# DrudePower.net
KiCad netlist of a schematic drawn in Altium Designer
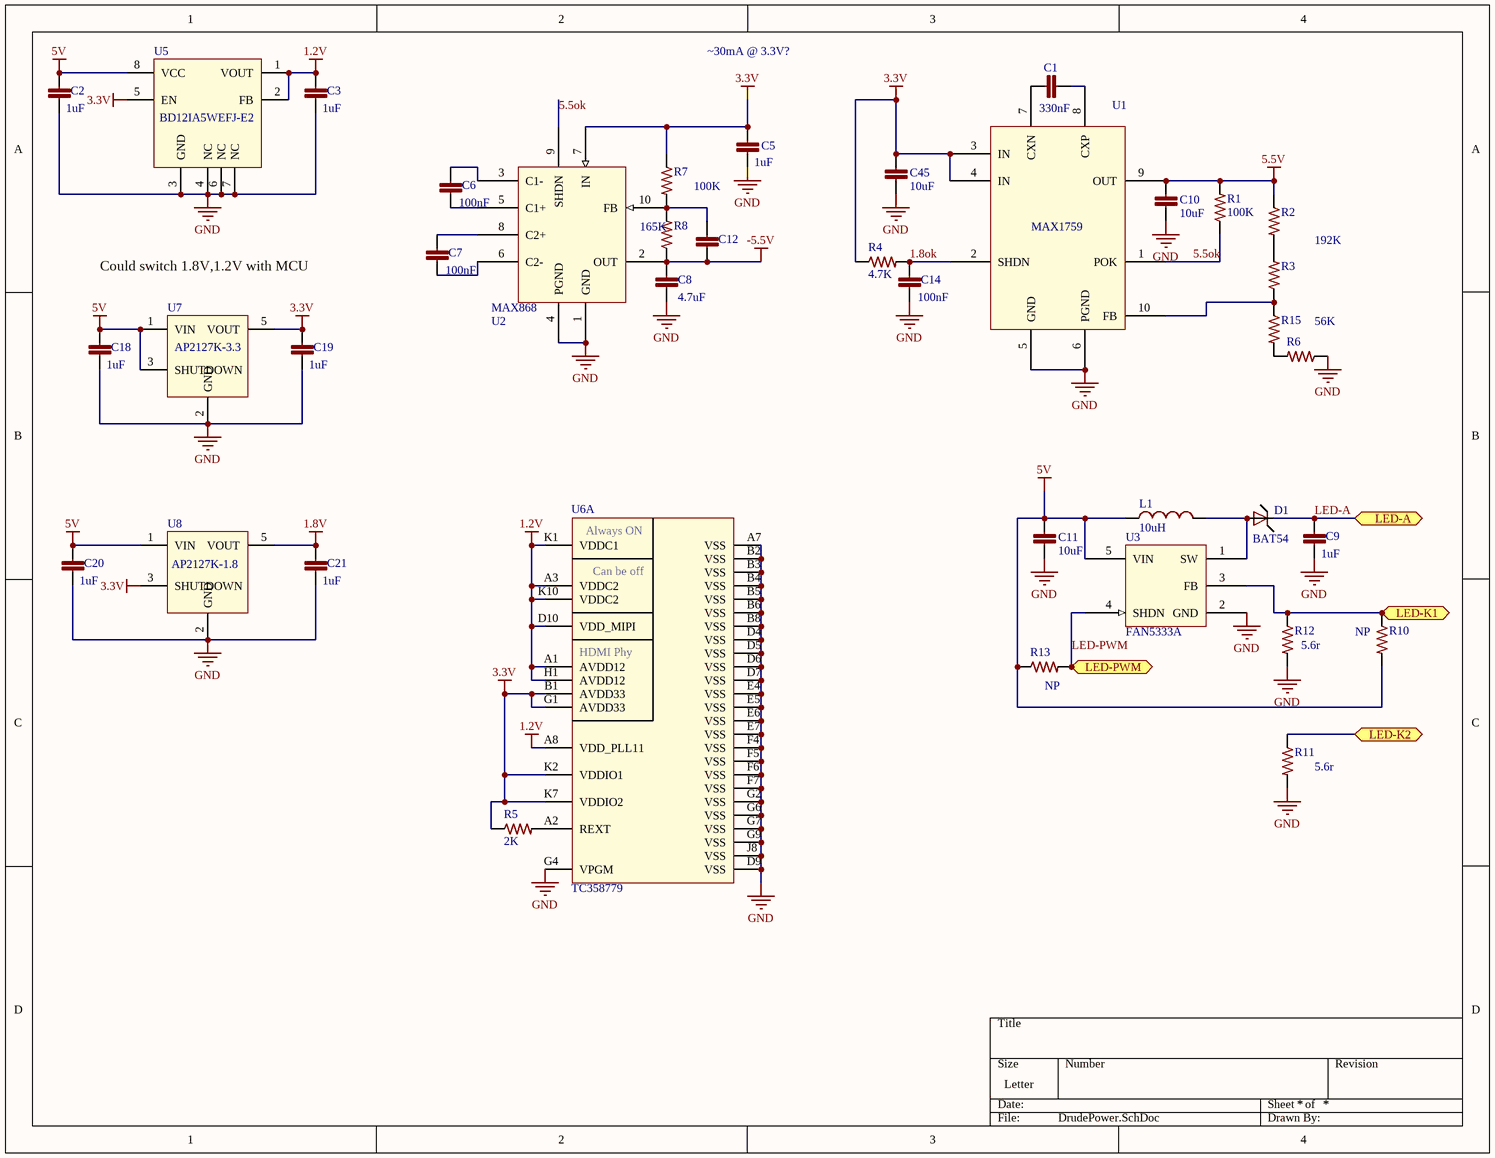
[diagram p0: DrudePower.SchDoc]

(export (version "E")
  (design (tool "Eeschema 10.0.6"))
  (components
    (comp (ref "C1")
      (value "330nF")
      (footprint "C0603")
      (description "CAP CER 0603 330nF 50V 10% X7R")
      (fields
        (field (name "MANUFACTURERPARTNUMBER") "C1608X7R1H334K080AC")
        (field (name "PUBLISHER") "UltiMachine")
      )
      (libsource (lib "hmi") (part "C1608X7R1H334K080AC"))
    )
    (comp (ref "C2")
      (value "1uF")
      (footprint "C0603")
      (description "CAP CER 0603 1uF 10V Y5V")
      (fields
        (field (name "MANUFACTURERPARTNUMBER") "CC0603ZRY5V6BB105")
        (field (name "PUBLISHER") "UltiMachine")
      )
      (libsource (lib "3Delight") (part "CC0603ZRY5V6BB105"))
    )
    (comp (ref "C3")
      (value "1uF")
      (footprint "C0603")
      (description "CAP CER 0603 1uF 10V Y5V")
      (fields
        (field (name "MANUFACTURERPARTNUMBER") "CC0603ZRY5V6BB105")
        (field (name "PUBLISHER") "UltiMachine")
      )
      (libsource (lib "3Delight") (part "CC0603ZRY5V6BB105"))
    )
    (comp (ref "C5")
      (value "1uF")
      (footprint "C0603")
      (description "CAP CER 0603 1uF 10V Y5V")
      (fields
        (field (name "MANUFACTURERPARTNUMBER") "CC0603ZRY5V6BB105")
        (field (name "PUBLISHER") "UltiMachine")
      )
      (libsource (lib "3Delight") (part "CC0603ZRY5V6BB105"))
    )
    (comp (ref "C6")
      (value "100nF")
      (footprint "C0603")
      (description "CAP CER 0603 100nF 50V 10% X7R")
      (fields
        (field (name "MANUFACTURERPARTNUMBER") "C0603C104K5RACTU")
        (field (name "PUBLISHER") "UltiMachine")
      )
      (libsource (lib "3Delight") (part "C0603C104K5RACTU"))
    )
    (comp (ref "C7")
      (value "100nF")
      (footprint "C0603")
      (description "CAP CER 0603 100nF 50V 10% X7R")
      (fields
        (field (name "MANUFACTURERPARTNUMBER") "C0603C104K5RACTU")
        (field (name "PUBLISHER") "UltiMachine")
      )
      (libsource (lib "3Delight") (part "C0603C104K5RACTU"))
    )
    (comp (ref "C8")
      (value "4.7uF")
      (footprint "C1206")
      (description "CAP CER 1206 4.7uF 50V 10% X7R")
      (fields
        (field (name "MANUFACTURERPARTNUMBER") "GRM31CR71H475KA12L")
        (field (name "PUBLISHER") "UltiMachine")
      )
      (libsource (lib "3Delight") (part "GRM31CR71H475KA12L"))
    )
    (comp (ref "C9")
      (value "1uF")
      (footprint "C0805")
      (description "CAP CER 0805 1uF 50V 10% X7R")
      (fields
        (field (name "MANUFACTURERPARTNUMBER") "GRM21BR71H105KA12L")
        (field (name "PUBLISHER") "UltiMachine")
      )
      (libsource (lib "3Delight") (part "GRM21BR71H105KA12L"))
    )
    (comp (ref "C10")
      (value "10uF")
      (footprint "C0805")
      (description "CAP CER 0805 10uF 10V 10% X5R")
      (fields
        (field (name "MANUFACTURERPARTNUMBER") "C0805C106K8PACTU")
        (field (name "PUBLISHER") "UltiMachine")
      )
      (libsource (lib "3Delight") (part "C0805C106K8PACTU"))
    )
    (comp (ref "C11")
      (value "10uF")
      (footprint "C0805")
      (description "CAP CER 0805 10uF 10V 10% X5R")
      (fields
        (field (name "MANUFACTURERPARTNUMBER") "C0805C106K8PACTU")
        (field (name "PUBLISHER") "UltiMachine")
      )
      (libsource (lib "3Delight") (part "C0805C106K8PACTU"))
    )
    (comp (ref "C12")
      (value "~")
      (footprint "C0603")
      (description "Capacitor Non Polarized")
      (fields (field (name "PUBLISHER") "UltiMachine"))
      (libsource (lib "3Delight") (part "Capacitor"))
    )
    (comp (ref "C14")
      (value "100nF")
      (footprint "C0603")
      (description "CAP CER 0603 100nF 50V 10% X7R")
      (fields
        (field (name "MANUFACTURERPARTNUMBER") "C0603C104K5RACTU")
        (field (name "PUBLISHER") "UltiMachine")
      )
      (libsource (lib "3Delight") (part "C0603C104K5RACTU"))
    )
    (comp (ref "C18")
      (value "1uF")
      (footprint "C0603")
      (description "CAP CER 0603 1uF 10V Y5V")
      (fields
        (field (name "MANUFACTURERPARTNUMBER") "CC0603ZRY5V6BB105")
        (field (name "PUBLISHER") "UltiMachine")
      )
      (libsource (lib "3Delight") (part "CC0603ZRY5V6BB105"))
    )
    (comp (ref "C19")
      (value "1uF")
      (footprint "C0603")
      (description "CAP CER 0603 1uF 10V Y5V")
      (fields
        (field (name "MANUFACTURERPARTNUMBER") "CC0603ZRY5V6BB105")
        (field (name "PUBLISHER") "UltiMachine")
      )
      (libsource (lib "3Delight") (part "CC0603ZRY5V6BB105"))
    )
    (comp (ref "C20")
      (value "1uF")
      (footprint "C0603")
      (description "CAP CER 0603 1uF 10V Y5V")
      (fields
        (field (name "MANUFACTURERPARTNUMBER") "CC0603ZRY5V6BB105")
        (field (name "PUBLISHER") "UltiMachine")
      )
      (libsource (lib "3Delight") (part "CC0603ZRY5V6BB105"))
    )
    (comp (ref "C21")
      (value "1uF")
      (footprint "C0603")
      (description "CAP CER 0603 1uF 10V Y5V")
      (fields
        (field (name "MANUFACTURERPARTNUMBER") "CC0603ZRY5V6BB105")
        (field (name "PUBLISHER") "UltiMachine")
      )
      (libsource (lib "3Delight") (part "CC0603ZRY5V6BB105"))
    )
    (comp (ref "C45")
      (value "10uF")
      (footprint "C0805")
      (description "CAP CER 0805 10uF 10V 10% X5R")
      (fields
        (field (name "MANUFACTURERPARTNUMBER") "C0805C106K8PACTU")
        (field (name "PUBLISHER") "UltiMachine")
      )
      (libsource (lib "3Delight") (part "C0805C106K8PACTU"))
    )
    (comp (ref "D1")
      (value "BAT54")
      (footprint "SOD523")
      (description "Diode Schottky 30V 200mA")
      (libsource (lib "hmi") (part "BAT54XV2"))
    )
    (comp (ref "L1")
      (value "10uH")
      (footprint "INDP3027X15L")
      (description "Ind 10uH 1A")
      (libsource (lib "hmi") (part "SRN3015-100M"))
    )
    (comp (ref "R1")
      (value "100K")
      (footprint "R0603")
      (description "RES 100K OHM 1/10W 1% 0603 SMD")
      (fields
        (field (name "MANUFACTURERPARTNUMBER") "RC0603FR-07100KL")
        (field (name "PUBLISHER") "UltiMachine")
      )
      (libsource (lib "3Delight") (part "RC0603FR-07100KL"))
    )
    (comp (ref "R2")
      (value "~")
      (footprint "R0603")
      (description "Resistor")
      (fields (field (name "PUBLISHER") "UltiMachine"))
      (libsource (lib "3Delight") (part "Resistor"))
    )
    (comp (ref "R3")
      (value "~")
      (footprint "R0603")
      (description "Resistor")
      (fields (field (name "PUBLISHER") "UltiMachine"))
      (libsource (lib "3Delight") (part "Resistor"))
    )
    (comp (ref "R4")
      (value "4.7K")
      (footprint "R0603")
      (description "RES 0603 4.7K 100mW 1%")
      (fields (field (name "MANUFACTURERPARTNUMBER") "ERJ3EKF4701V") (field (name "PUBLISHER") "UltiMachine"))
      (libsource (lib "3Delight") (part "ERJ3EKF4701V"))
    )
    (comp (ref "R5")
      (value "2K")
      (footprint "R0402")
      (description "RES SMD 2K OHM 1% 1/16W 0402")
      (fields
        (field (name "MANUFACTURERPARTNUMBER") "RC0402FR-0710KP")
        (field (name "PUBLISHER") "UltiMachine")
      )
      (libsource (lib "3Delight") (part "RC0402FR-072KL"))
    )
    (comp (ref "R6")
      (value "~")
      (footprint "R0603")
      (description "Resistor")
      (fields (field (name "PUBLISHER") "UltiMachine"))
      (libsource (lib "3Delight") (part "Resistor"))
    )
    (comp (ref "R7")
      (value "~")
      (footprint "R0603")
      (description "Resistor")
      (fields (field (name "PUBLISHER") "UltiMachine"))
      (libsource (lib "3Delight") (part "Resistor"))
    )
    (comp (ref "R8")
      (value "~")
      (footprint "R0603")
      (description "Resistor")
      (fields (field (name "PUBLISHER") "UltiMachine"))
      (libsource (lib "3Delight") (part "Resistor"))
    )
    (comp (ref "R10")
      (value "~")
      (footprint "R0603")
      (description "Resistor")
      (fields (field (name "PUBLISHER") "UltiMachine"))
      (libsource (lib "3Delight") (part "Resistor"))
    )
    (comp (ref "R11")
      (value "~")
      (footprint "R0603")
      (description "Resistor")
      (fields (field (name "PUBLISHER") "UltiMachine"))
      (libsource (lib "3Delight") (part "Resistor"))
    )
    (comp (ref "R12")
      (value "~")
      (footprint "R0603")
      (description "Resistor")
      (fields (field (name "PUBLISHER") "UltiMachine"))
      (libsource (lib "3Delight") (part "Resistor"))
    )
    (comp (ref "R13")
      (value "~")
      (footprint "R0603")
      (description "Resistor")
      (fields (field (name "PUBLISHER") "UltiMachine"))
      (libsource (lib "3Delight") (part "Resistor"))
    )
    (comp (ref "R15")
      (value "~")
      (footprint "R0603")
      (description "Resistor")
      (fields (field (name "PUBLISHER") "UltiMachine"))
      (libsource (lib "3Delight") (part "Resistor"))
    )
    (comp (ref "U1")
      (value "MAX1759")
      (footprint "TSSOP50P490X109-10L")
      (description "Buck/Boost Regulating Charge Pump")
      (libsource (lib "hmi") (part "MAX1759"))
    )
    (comp (ref "U2")
      (value "MAX868")
      (footprint "TSSOP50P490X109-10L")
      (description "Regulated -2x Inverting Charge Pump")
      (libsource (lib "hmi") (part "MAX868"))
    )
    (comp (ref "U3")
      (value "FAN5333A")
      (footprint "SOT95P270X145-5L")
      (description "LED Driver w/ integrated switch")
      (libsource (lib "hmi") (part "FAN5333"))
    )
    (comp (ref "U5")
      (value "BD12IA5WEFJ-E2")
      (footprint "TSOP-HTSOP-J8-127P600X100_HS-9M")
      (description "LDO Regulator 500mA 1.2V")
      (libsource (lib "hmi") (part "BD12IA5WEFJ-E2"))
    )
    (comp (ref "U6")
      (value "TC358779")
      (footprint "BGA80-0707-065")
      (libsource (lib "hmi") (part "TC358779"))
    )
    (comp (ref "U7")
      (value "AP2127K-3.3")
      (footprint "hmi:SOT23-5P285X140-5L")
      (description "LDO 3.3V 0.3A SOT25")
      (libsource (lib "hmi") (part "AP2127K-3.3TRG1"))
    )
    (comp (ref "U8")
      (value "AP2127K-1.8")
      (footprint "hmi:SOT23-5P285X140-5L")
      (description "LDO 1.8V 0.3A SOT25")
      (libsource (lib "hmi") (part "AP2127K-1.8TRG1"))
    )
  )
  (nets
    (net (code "1") (name "-5.5V") (class "Default")
      (node (ref "C12") (pin "2") (pinfunction "2_2") (pintype "passive"))
      (node (ref "C8") (pin "1") (pinfunction "1_1") (pintype "passive"))
      (node (ref "R8") (pin "1") (pinfunction "1_1") (pintype "passive"))
      (node (ref "U2") (pin "2") (pinfunction "OUT_2") (pintype "passive"))
    )
    (net (code "2") (name "/1.8ok") (class "Default")
      (node (ref "C14") (pin "1") (pinfunction "1_1") (pintype "passive"))
      (node (ref "R4") (pin "2") (pinfunction "2_2") (pintype "passive"))
      (node (ref "U1") (pin "2") (pinfunction "SHDN_2") (pintype "passive"))
    )
    (net (code "3") (name "/5.5ok") (class "Default")
      (node (ref "R1") (pin "1") (pinfunction "1_1") (pintype "passive"))
      (node (ref "U1") (pin "1") (pinfunction "POK_1") (pintype "passive"))
      (node (ref "U2") (pin "9") (pinfunction "SHDN_9") (pintype "passive"))
    )
    (net (code "4") (name "/LED-A") (class "Default")
      (node (ref "C9") (pin "1") (pinfunction "1_1") (pintype "passive"))
      (node (ref "D1") (pin "C") (pinfunction "C_C") (pintype "passive"))
    )
    (net (code "5") (name "/LED-K1") (class "Default")
      (node (ref "R10") (pin "1") (pinfunction "1_1") (pintype "passive"))
      (node (ref "R12") (pin "1") (pinfunction "1_1") (pintype "passive"))
      (node (ref "U3") (pin "3") (pinfunction "FB_3") (pintype "passive"))
    )
    (net (code "6") (name "/LED-K2") (class "Default")
      (node (ref "R11") (pin "1") (pinfunction "1_1") (pintype "passive"))
    )
    (net (code "7") (name "/LED-PWM") (class "Default")
      (node (ref "R13") (pin "2") (pinfunction "2_2") (pintype "passive"))
      (node (ref "U3") (pin "4") (pinfunction "SHDN_4") (pintype "input"))
    )
    (net (code "8") (name "1.2V") (class "Default")
      (node (ref "C3") (pin "1") (pinfunction "1_1") (pintype "passive"))
      (node (ref "U5") (pin "1") (pinfunction "VOUT_1") (pintype "power_in"))
      (node (ref "U5") (pin "2") (pinfunction "FB_2") (pintype "power_in"))
      (node (ref "U6") (pin "A1") (pinfunction "AVDD12_A1") (pintype "power_in"))
      (node (ref "U6") (pin "A3") (pinfunction "VDDC2_A3") (pintype "power_in"))
      (node (ref "U6") (pin "A8") (pinfunction "VDD_PLL11_A8") (pintype "power_in"))
      (node (ref "U6") (pin "D10") (pinfunction "VDD_MIPI_D10") (pintype "power_in"))
      (node (ref "U6") (pin "H1") (pinfunction "AVDD12_H1") (pintype "power_in"))
      (node (ref "U6") (pin "K1") (pinfunction "VDDC1_K1") (pintype "power_in"))
      (node (ref "U6") (pin "K10") (pinfunction "VDDC2_K10") (pintype "power_in"))
    )
    (net (code "9") (name "1.8V") (class "Default")
      (node (ref "C21") (pin "1") (pinfunction "1_1") (pintype "passive"))
      (node (ref "U8") (pin "5") (pinfunction "VOUT_5") (pintype "power_in"))
    )
    (net (code "10") (name "3.3V") (class "Default")
      (node (ref "C19") (pin "1") (pinfunction "1_1") (pintype "passive"))
      (node (ref "C45") (pin "1") (pinfunction "1_1") (pintype "passive"))
      (node (ref "C5") (pin "1") (pinfunction "1_1") (pintype "passive"))
      (node (ref "R4") (pin "1") (pinfunction "1_1") (pintype "passive"))
      (node (ref "R5") (pin "1") (pinfunction "1_1") (pintype "passive"))
      (node (ref "R7") (pin "1") (pinfunction "1_1") (pintype "passive"))
      (node (ref "U1") (pin "3") (pinfunction "IN_3") (pintype "power_in"))
      (node (ref "U1") (pin "4") (pinfunction "IN_4") (pintype "power_in"))
      (node (ref "U2") (pin "7") (pinfunction "IN_7") (pintype "input"))
      (node (ref "U5") (pin "5") (pinfunction "EN_5") (pintype "power_in"))
      (node (ref "U6") (pin "B1") (pinfunction "AVDD33_B1") (pintype "power_in"))
      (node (ref "U6") (pin "G1") (pinfunction "AVDD33_G1") (pintype "power_in"))
      (node (ref "U6") (pin "K2") (pinfunction "VDDIO1_K2") (pintype "power_in"))
      (node (ref "U6") (pin "K7") (pinfunction "VDDIO2_K7") (pintype "power_in"))
      (node (ref "U7") (pin "5") (pinfunction "VOUT_5") (pintype "power_in"))
      (node (ref "U8") (pin "3") (pinfunction "SHUTDOWN_3") (pintype "power_in"))
    )
    (net (code "11") (name "5.5V") (class "Default")
      (node (ref "C10") (pin "1") (pinfunction "1_1") (pintype "passive"))
      (node (ref "R1") (pin "2") (pinfunction "2_2") (pintype "passive"))
      (node (ref "R2") (pin "1") (pinfunction "1_1") (pintype "passive"))
      (node (ref "U1") (pin "9") (pinfunction "OUT_9") (pintype "power_in"))
    )
    (net (code "12") (name "5V") (class "Default")
      (node (ref "C11") (pin "1") (pinfunction "1_1") (pintype "passive"))
      (node (ref "C18") (pin "1") (pinfunction "1_1") (pintype "passive"))
      (node (ref "C2") (pin "1") (pinfunction "1_1") (pintype "passive"))
      (node (ref "C20") (pin "1") (pinfunction "1_1") (pintype "passive"))
      (node (ref "L1") (pin "1") (pinfunction "1_1") (pintype "passive"))
      (node (ref "R10") (pin "2") (pinfunction "2_2") (pintype "passive"))
      (node (ref "R13") (pin "1") (pinfunction "1_1") (pintype "passive"))
      (node (ref "U3") (pin "5") (pinfunction "VIN_5") (pintype "power_in"))
      (node (ref "U5") (pin "8") (pinfunction "VCC_8") (pintype "power_in"))
      (node (ref "U7") (pin "1") (pinfunction "VIN_1") (pintype "power_in"))
      (node (ref "U7") (pin "3") (pinfunction "SHUTDOWN_3") (pintype "power_in"))
      (node (ref "U8") (pin "1") (pinfunction "VIN_1") (pintype "power_in"))
    )
    (net (code "13") (name "GND") (class "Default")
      (node (ref "C10") (pin "2") (pinfunction "2_2") (pintype "passive"))
      (node (ref "C11") (pin "2") (pinfunction "2_2") (pintype "passive"))
      (node (ref "C14") (pin "2") (pinfunction "2_2") (pintype "passive"))
      (node (ref "C18") (pin "2") (pinfunction "2_2") (pintype "passive"))
      (node (ref "C19") (pin "2") (pinfunction "2_2") (pintype "passive"))
      (node (ref "C2") (pin "2") (pinfunction "2_2") (pintype "passive"))
      (node (ref "C20") (pin "2") (pinfunction "2_2") (pintype "passive"))
      (node (ref "C21") (pin "2") (pinfunction "2_2") (pintype "passive"))
      (node (ref "C3") (pin "2") (pinfunction "2_2") (pintype "passive"))
      (node (ref "C45") (pin "2") (pinfunction "2_2") (pintype "passive"))
      (node (ref "C5") (pin "2") (pinfunction "2_2") (pintype "passive"))
      (node (ref "C8") (pin "2") (pinfunction "2_2") (pintype "passive"))
      (node (ref "C9") (pin "2") (pinfunction "2_2") (pintype "passive"))
      (node (ref "R11") (pin "2") (pinfunction "2_2") (pintype "passive"))
      (node (ref "R12") (pin "2") (pinfunction "2_2") (pintype "passive"))
      (node (ref "R6") (pin "1") (pinfunction "1_1") (pintype "passive"))
      (node (ref "U1") (pin "5") (pinfunction "GND_5") (pintype "power_in"))
      (node (ref "U1") (pin "6") (pinfunction "PGND_6") (pintype "power_in"))
      (node (ref "U2") (pin "1") (pinfunction "GND_1") (pintype "power_in"))
      (node (ref "U2") (pin "4") (pinfunction "PGND_4") (pintype "power_in"))
      (node (ref "U3") (pin "2") (pinfunction "GND_2") (pintype "power_in"))
      (node (ref "U5") (pin "3") (pinfunction "GND_3") (pintype "power_in"))
      (node (ref "U5") (pin "4") (pinfunction "NC_4") (pintype "power_in"))
      (node (ref "U5") (pin "6") (pinfunction "NC_6") (pintype "power_in"))
      (node (ref "U5") (pin "7") (pinfunction "NC_7") (pintype "power_in"))
      (node (ref "U6") (pin "A7") (pinfunction "VSS_A7") (pintype "power_in"))
      (node (ref "U6") (pin "B2") (pinfunction "VSS_B2") (pintype "power_in"))
      (node (ref "U6") (pin "B3") (pinfunction "VSS_B3") (pintype "power_in"))
      (node (ref "U6") (pin "B4") (pinfunction "VSS_B4") (pintype "power_in"))
      (node (ref "U6") (pin "B5") (pinfunction "VSS_B5") (pintype "power_in"))
      (node (ref "U6") (pin "B6") (pinfunction "VSS_B6") (pintype "power_in"))
      (node (ref "U6") (pin "B8") (pinfunction "VSS_B8") (pintype "power_in"))
      (node (ref "U6") (pin "D4") (pinfunction "VSS_D4") (pintype "power_in"))
      (node (ref "U6") (pin "D5") (pinfunction "VSS_D5") (pintype "power_in"))
      (node (ref "U6") (pin "D6") (pinfunction "VSS_D6") (pintype "power_in"))
      (node (ref "U6") (pin "D7") (pinfunction "VSS_D7") (pintype "power_in"))
      (node (ref "U6") (pin "D9") (pinfunction "VSS_D9") (pintype "power_in"))
      (node (ref "U6") (pin "E4") (pinfunction "VSS_E4") (pintype "power_in"))
      (node (ref "U6") (pin "E5") (pinfunction "VSS_E5") (pintype "power_in"))
      (node (ref "U6") (pin "E6") (pinfunction "VSS_E6") (pintype "power_in"))
      (node (ref "U6") (pin "E7") (pinfunction "VSS_E7") (pintype "power_in"))
      (node (ref "U6") (pin "F4") (pinfunction "VSS_F4") (pintype "power_in"))
      (node (ref "U6") (pin "F5") (pinfunction "VSS_F5") (pintype "power_in"))
      (node (ref "U6") (pin "F6") (pinfunction "VSS_F6") (pintype "power_in"))
      (node (ref "U6") (pin "F7") (pinfunction "VSS_F7") (pintype "power_in"))
      (node (ref "U6") (pin "G2") (pinfunction "VSS_G2") (pintype "power_in"))
      (node (ref "U6") (pin "G4") (pinfunction "VPGM_G4") (pintype "power_in"))
      (node (ref "U6") (pin "G6") (pinfunction "VSS_G6") (pintype "power_in"))
      (node (ref "U6") (pin "G7") (pinfunction "VSS_G7") (pintype "power_in"))
      (node (ref "U6") (pin "G9") (pinfunction "VSS_G9") (pintype "power_in"))
      (node (ref "U6") (pin "J8") (pinfunction "VSS_J8") (pintype "power_in"))
      (node (ref "U7") (pin "2") (pinfunction "GND_2") (pintype "power_in"))
      (node (ref "U8") (pin "2") (pinfunction "GND_2") (pintype "power_in"))
    )
    (net (code "14") (name "Net-(R2-Pad2)") (class "Default")
      (node (ref "R2") (pin "2") (pinfunction "2_2") (pintype "passive"))
      (node (ref "R3") (pin "2") (pinfunction "2_2") (pintype "passive"))
    )
    (net (code "15") (name "Net-(R15-Pad2)") (class "Default")
      (node (ref "R15") (pin "2") (pinfunction "2_2") (pintype "passive"))
      (node (ref "R6") (pin "2") (pinfunction "2_2") (pintype "passive"))
    )
    (net (code "16") (name "Net-(U1-CXN)") (class "Default")
      (node (ref "C1") (pin "1") (pinfunction "1_1") (pintype "passive"))
      (node (ref "U1") (pin "7") (pinfunction "CXN_7") (pintype "passive"))
    )
    (net (code "17") (name "Net-(U1-CXP)") (class "Default")
      (node (ref "C1") (pin "2") (pinfunction "2_2") (pintype "passive"))
      (node (ref "U1") (pin "8") (pinfunction "CXP_8") (pintype "passive"))
    )
    (net (code "18") (name "Net-(U1-FB)") (class "Default")
      (node (ref "R15") (pin "1") (pinfunction "1_1") (pintype "passive"))
      (node (ref "R3") (pin "1") (pinfunction "1_1") (pintype "passive"))
      (node (ref "U1") (pin "10") (pinfunction "FB_10") (pintype "power_in"))
    )
    (net (code "19") (name "Net-(U2-C1+)") (class "Default")
      (node (ref "C6") (pin "2") (pinfunction "2_2") (pintype "passive"))
      (node (ref "U2") (pin "5") (pinfunction "C1+_5") (pintype "power_in"))
    )
    (net (code "20") (name "Net-(U2-C1-)") (class "Default")
      (node (ref "C6") (pin "1") (pinfunction "1_1") (pintype "passive"))
      (node (ref "U2") (pin "3") (pinfunction "C1-_3") (pintype "passive"))
    )
    (net (code "21") (name "Net-(U2-C2+)") (class "Default")
      (node (ref "C7") (pin "1") (pinfunction "1_1") (pintype "passive"))
      (node (ref "U2") (pin "8") (pinfunction "C2+_8") (pintype "passive"))
    )
    (net (code "22") (name "Net-(U2-C2-)") (class "Default")
      (node (ref "C7") (pin "2") (pinfunction "2_2") (pintype "passive"))
      (node (ref "U2") (pin "6") (pinfunction "C2-_6") (pintype "passive"))
    )
    (net (code "23") (name "Net-(U2-FB)") (class "Default")
      (node (ref "C12") (pin "1") (pinfunction "1_1") (pintype "passive"))
      (node (ref "R7") (pin "2") (pinfunction "2_2") (pintype "passive"))
      (node (ref "R8") (pin "2") (pinfunction "2_2") (pintype "passive"))
      (node (ref "U2") (pin "10") (pinfunction "FB_10") (pintype "input"))
    )
    (net (code "24") (name "Net-(U3-SW)") (class "Default")
      (node (ref "D1") (pin "A") (pinfunction "A_A") (pintype "passive"))
      (node (ref "L1") (pin "2") (pinfunction "2_2") (pintype "passive"))
      (node (ref "U3") (pin "1") (pinfunction "SW_1") (pintype "power_in"))
    )
    (net (code "25") (name "Net-(U6A-REXT)") (class "Default")
      (node (ref "R5") (pin "2") (pinfunction "2_2") (pintype "passive"))
      (node (ref "U6") (pin "A2") (pinfunction "REXT_A2") (pintype "power_in"))
    )
  )
)
